# Ekspander.net
KiCad netlist of a schematic drawn in EAGLE
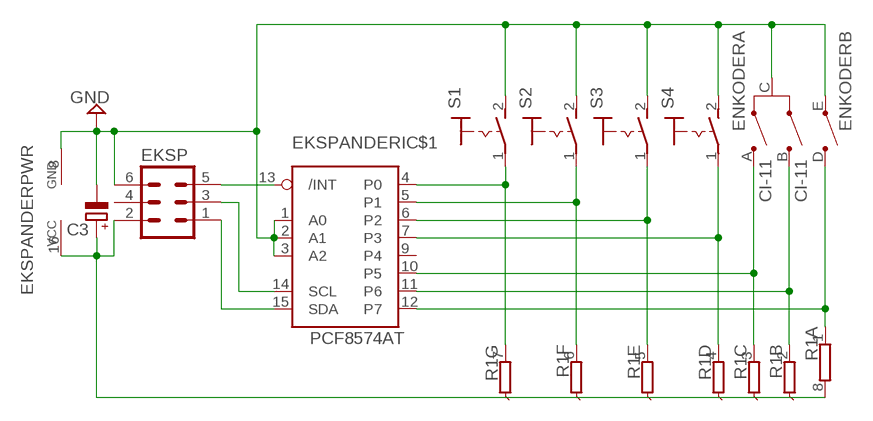
[diagram p0: schematic, sheet 1]

(export (version "E")
  (design (tool "Eeschema 10.0.6"))
  (components
    (comp (ref "C3")
      (value "CPOL-EU140CLH-1010")
      (footprint "eagle-import:140CLH-1010")
      (libsource (lib "eagle-import") (part "CPOL-EU140CLH-1010"))
    )
    (comp (ref "EKSP")
      (value "ML6")
      (footprint "eagle-import:ML6")
      (libsource (lib "eagle-import") (part "ML6"))
    )
    (comp (ref "EKSPANDER")
      (value "PCF8574AT")
      (footprint "eagle-import:SO16")
      (libsource (lib "eagle-import") (part "PCF8574AT"))
    )
    (comp (ref "ENKODER")
      (value "CI-11")
      (footprint "eagle-import:CI-11")
      (libsource (lib "eagle-import") (part "CI-11"))
    )
    (comp (ref "R1")
      (value "2NBS08-7E")
      (footprint "eagle-import:SO8")
      (libsource (lib "eagle-import") (part "2NBS08-7E"))
    )
    (comp (ref "S1")
      (value "MS243")
      (footprint "eagle-import:MS243")
      (libsource (lib "eagle-import") (part "MS243"))
    )
    (comp (ref "S2")
      (value "MS243")
      (footprint "eagle-import:MS243")
      (libsource (lib "eagle-import") (part "MS243"))
    )
    (comp (ref "S3")
      (value "MS243")
      (footprint "eagle-import:MS243")
      (libsource (lib "eagle-import") (part "MS243"))
    )
    (comp (ref "S4")
      (value "MS243")
      (footprint "eagle-import:MS243")
      (libsource (lib "eagle-import") (part "MS243"))
    )
  )
  (nets
    (net (code "1") (name "GND") (class "Default")
      (node (ref "C3") (pin "-") (pinfunction "-_-") (pintype "passive"))
      (node (ref "EKSP") (pin "6") (pinfunction "6_6") (pintype "passive"))
      (node (ref "EKSPANDER") (pin "1") (pinfunction "A0_1") (pintype "input"))
      (node (ref "EKSPANDER") (pin "2") (pinfunction "A1_2") (pintype "input"))
      (node (ref "EKSPANDER") (pin "3") (pinfunction "A2_3") (pintype "input"))
      (node (ref "EKSPANDER") (pin "8") (pinfunction "GND_8") (pintype "power_in"))
      (node (ref "ENKODER") (pin "C") (pinfunction "C_C") (pintype "passive"))
      (node (ref "ENKODER") (pin "E") (pinfunction "E_E") (pintype "passive"))
      (node (ref "S1") (pin "2") (pinfunction "S_2") (pintype "passive"))
      (node (ref "S2") (pin "2") (pinfunction "S_2") (pintype "passive"))
      (node (ref "S3") (pin "2") (pinfunction "S_2") (pintype "passive"))
      (node (ref "S4") (pin "2") (pinfunction "S_2") (pintype "passive"))
    )
    (net (code "2") (name "Net-(EKSPANDERA-P0)") (class "Default")
      (node (ref "EKSPANDER") (pin "4") (pinfunction "P0_4") (pintype "bidirectional"))
      (node (ref "R1") (pin "7") (pinfunction "1_7") (pintype "passive"))
      (node (ref "S1") (pin "1") (pinfunction "P_1") (pintype "passive"))
    )
    (net (code "3") (name "Net-(EKSPANDERA-P1)") (class "Default")
      (node (ref "EKSPANDER") (pin "5") (pinfunction "P1_5") (pintype "bidirectional"))
      (node (ref "R1") (pin "6") (pinfunction "1_6") (pintype "passive"))
      (node (ref "S2") (pin "1") (pinfunction "P_1") (pintype "passive"))
    )
    (net (code "4") (name "Net-(EKSPANDERA-P2)") (class "Default")
      (node (ref "EKSPANDER") (pin "6") (pinfunction "P2_6") (pintype "bidirectional"))
      (node (ref "R1") (pin "5") (pinfunction "1_5") (pintype "passive"))
      (node (ref "S3") (pin "1") (pinfunction "P_1") (pintype "passive"))
    )
    (net (code "5") (name "Net-(EKSPANDERA-P3)") (class "Default")
      (node (ref "EKSPANDER") (pin "7") (pinfunction "P3_7") (pintype "bidirectional"))
      (node (ref "R1") (pin "4") (pinfunction "1_4") (pintype "passive"))
      (node (ref "S4") (pin "1") (pinfunction "P_1") (pintype "passive"))
    )
    (net (code "6") (name "Net-(EKSPANDERA-P5)") (class "Default")
      (node (ref "EKSPANDER") (pin "10") (pinfunction "P5_10") (pintype "bidirectional"))
      (node (ref "ENKODER") (pin "A") (pinfunction "A_A") (pintype "passive"))
      (node (ref "R1") (pin "3") (pinfunction "1_3") (pintype "passive"))
    )
    (net (code "7") (name "Net-(EKSPANDERA-P6)") (class "Default")
      (node (ref "EKSPANDER") (pin "11") (pinfunction "P6_11") (pintype "bidirectional"))
      (node (ref "ENKODER") (pin "B") (pinfunction "B_B") (pintype "passive"))
      (node (ref "R1") (pin "2") (pinfunction "1_2") (pintype "passive"))
    )
    (net (code "8") (name "Net-(EKSPANDERA-P7)") (class "Default")
      (node (ref "EKSPANDER") (pin "12") (pinfunction "P7_12") (pintype "bidirectional"))
      (node (ref "ENKODER") (pin "D") (pinfunction "D_D") (pintype "passive"))
      (node (ref "R1") (pin "1") (pinfunction "1_1") (pintype "passive"))
    )
    (net (code "9") (name "Net-(EKSPANDERA-SCL)") (class "Default")
      (node (ref "EKSP") (pin "3") (pinfunction "3_3") (pintype "passive"))
      (node (ref "EKSPANDER") (pin "14") (pinfunction "SCL_14") (pintype "input"))
    )
    (net (code "10") (name "Net-(EKSPANDERA-SDA)") (class "Default")
      (node (ref "EKSP") (pin "1") (pinfunction "1_1") (pintype "passive"))
      (node (ref "EKSPANDER") (pin "15") (pinfunction "SDA_15") (pintype "bidirectional"))
    )
    (net (code "11") (name "Net-(EKSPANDERA-{slash}INT)") (class "Default")
      (node (ref "EKSP") (pin "5") (pinfunction "5_5") (pintype "passive"))
      (node (ref "EKSPANDER") (pin "13") (pinfunction "/INT_13") (pintype "output"))
    )
    (net (code "12") (name "Net-(EKSPANDERB-VCC)") (class "Default")
      (node (ref "C3") (pin "+") (pinfunction "+_+") (pintype "passive"))
      (node (ref "EKSP") (pin "2") (pinfunction "2_2") (pintype "passive"))
      (node (ref "EKSPANDER") (pin "16") (pinfunction "VCC_16") (pintype "power_in"))
      (node (ref "R1") (pin "8") (pinfunction "2_8") (pintype "passive"))
    )
    (net (code "13") (name "unconnected-(EKSP-Pad4)") (class "Default")
      (node (ref "EKSP") (pin "4") (pinfunction "4_4") (pintype "passive"))
    )
    (net (code "14") (name "unconnected-(EKSPANDERA-P4-Pad9)") (class "Default")
      (node (ref "EKSPANDER") (pin "9") (pinfunction "P4_9") (pintype "bidirectional"))
    )
  )
)
